# QuadroMIDI.net
KiCad netlist of a schematic drawn in EAGLE
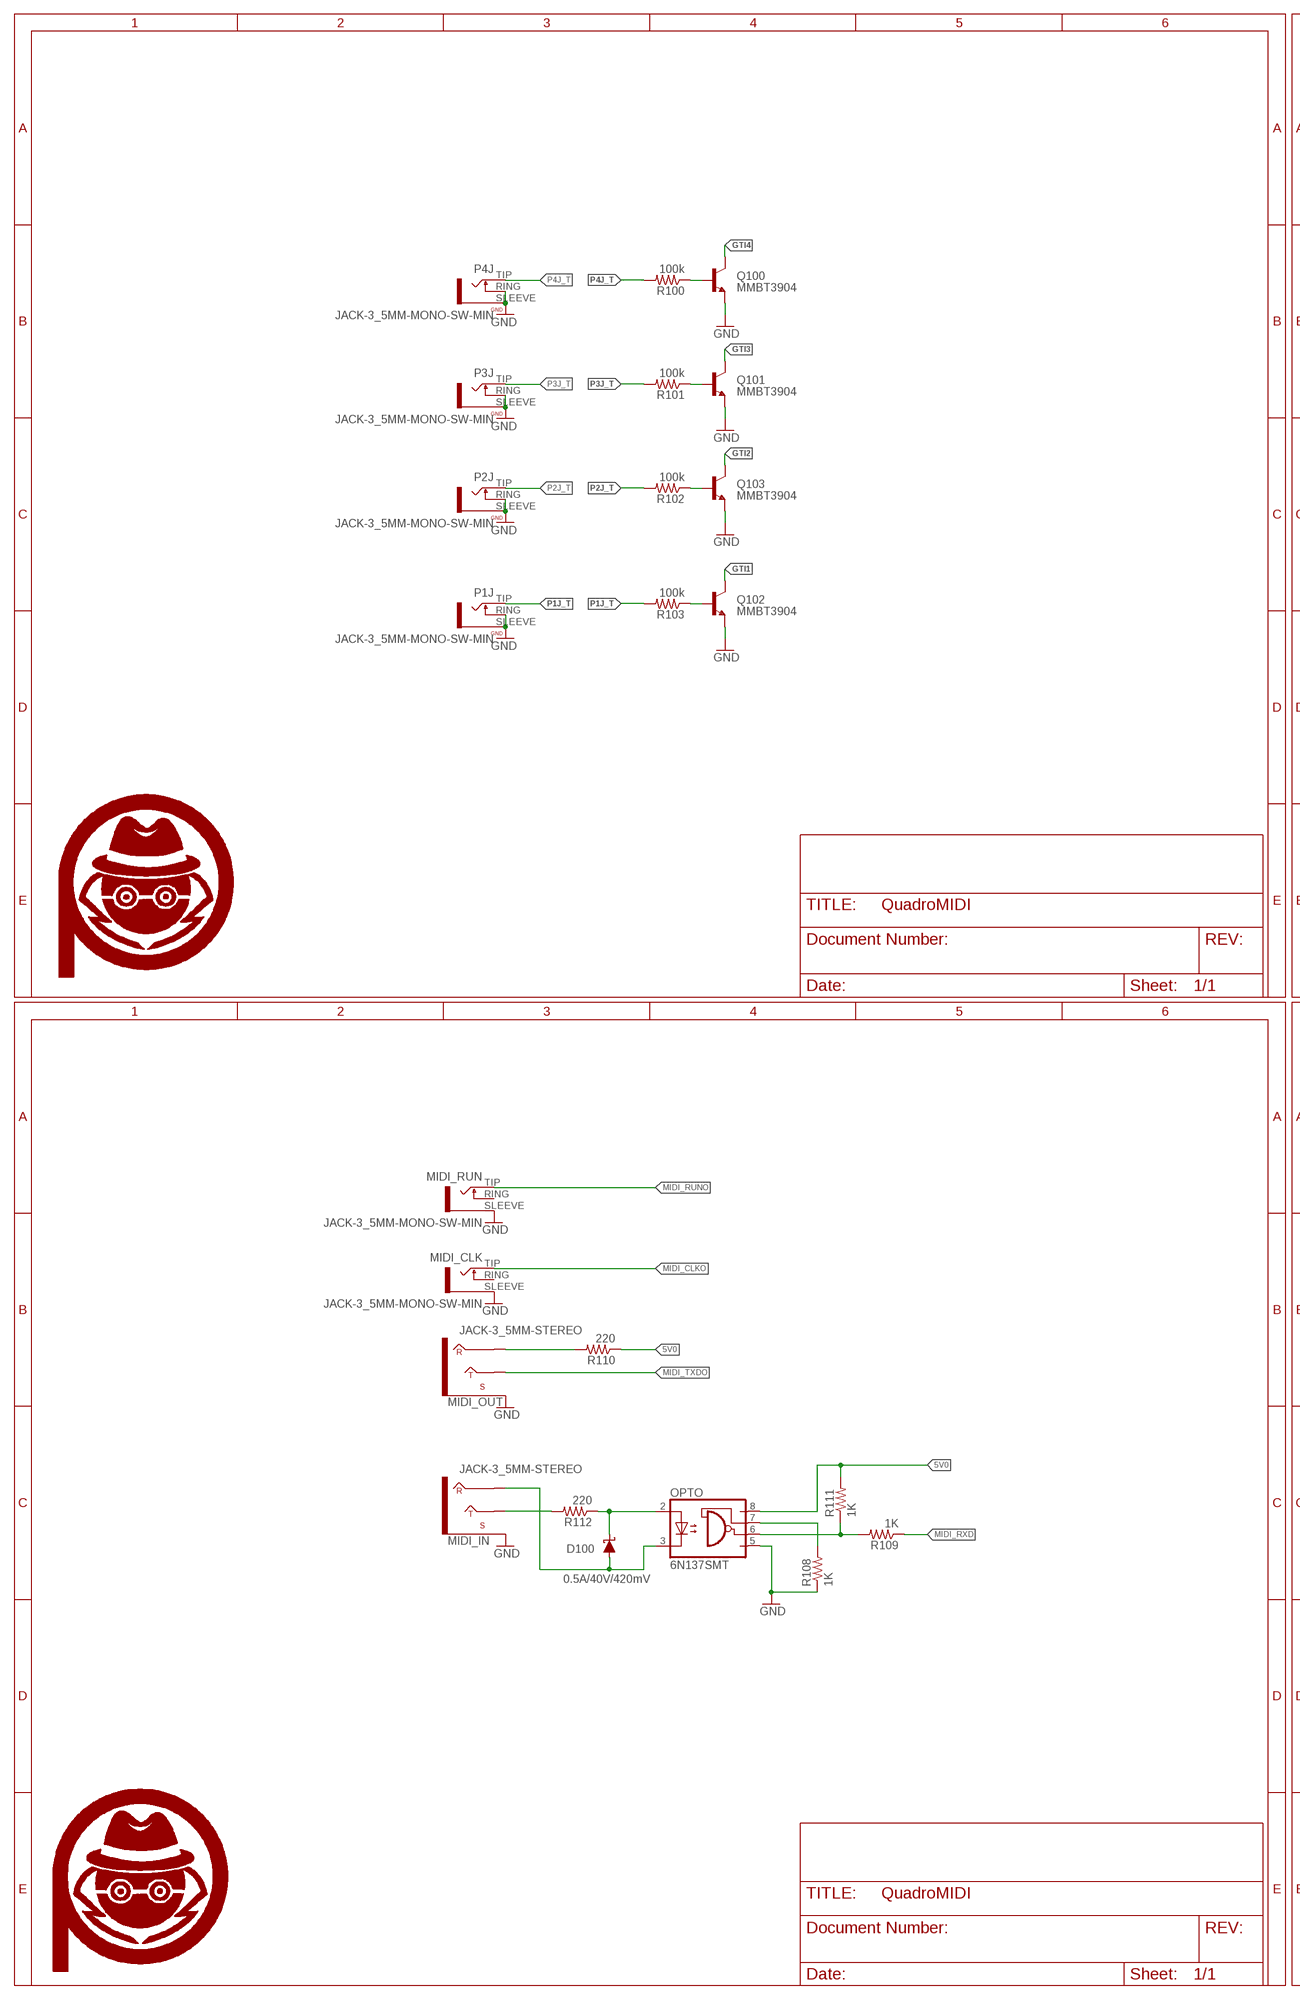
[diagram p0: schematic, sheet 1, part 1 of 2]
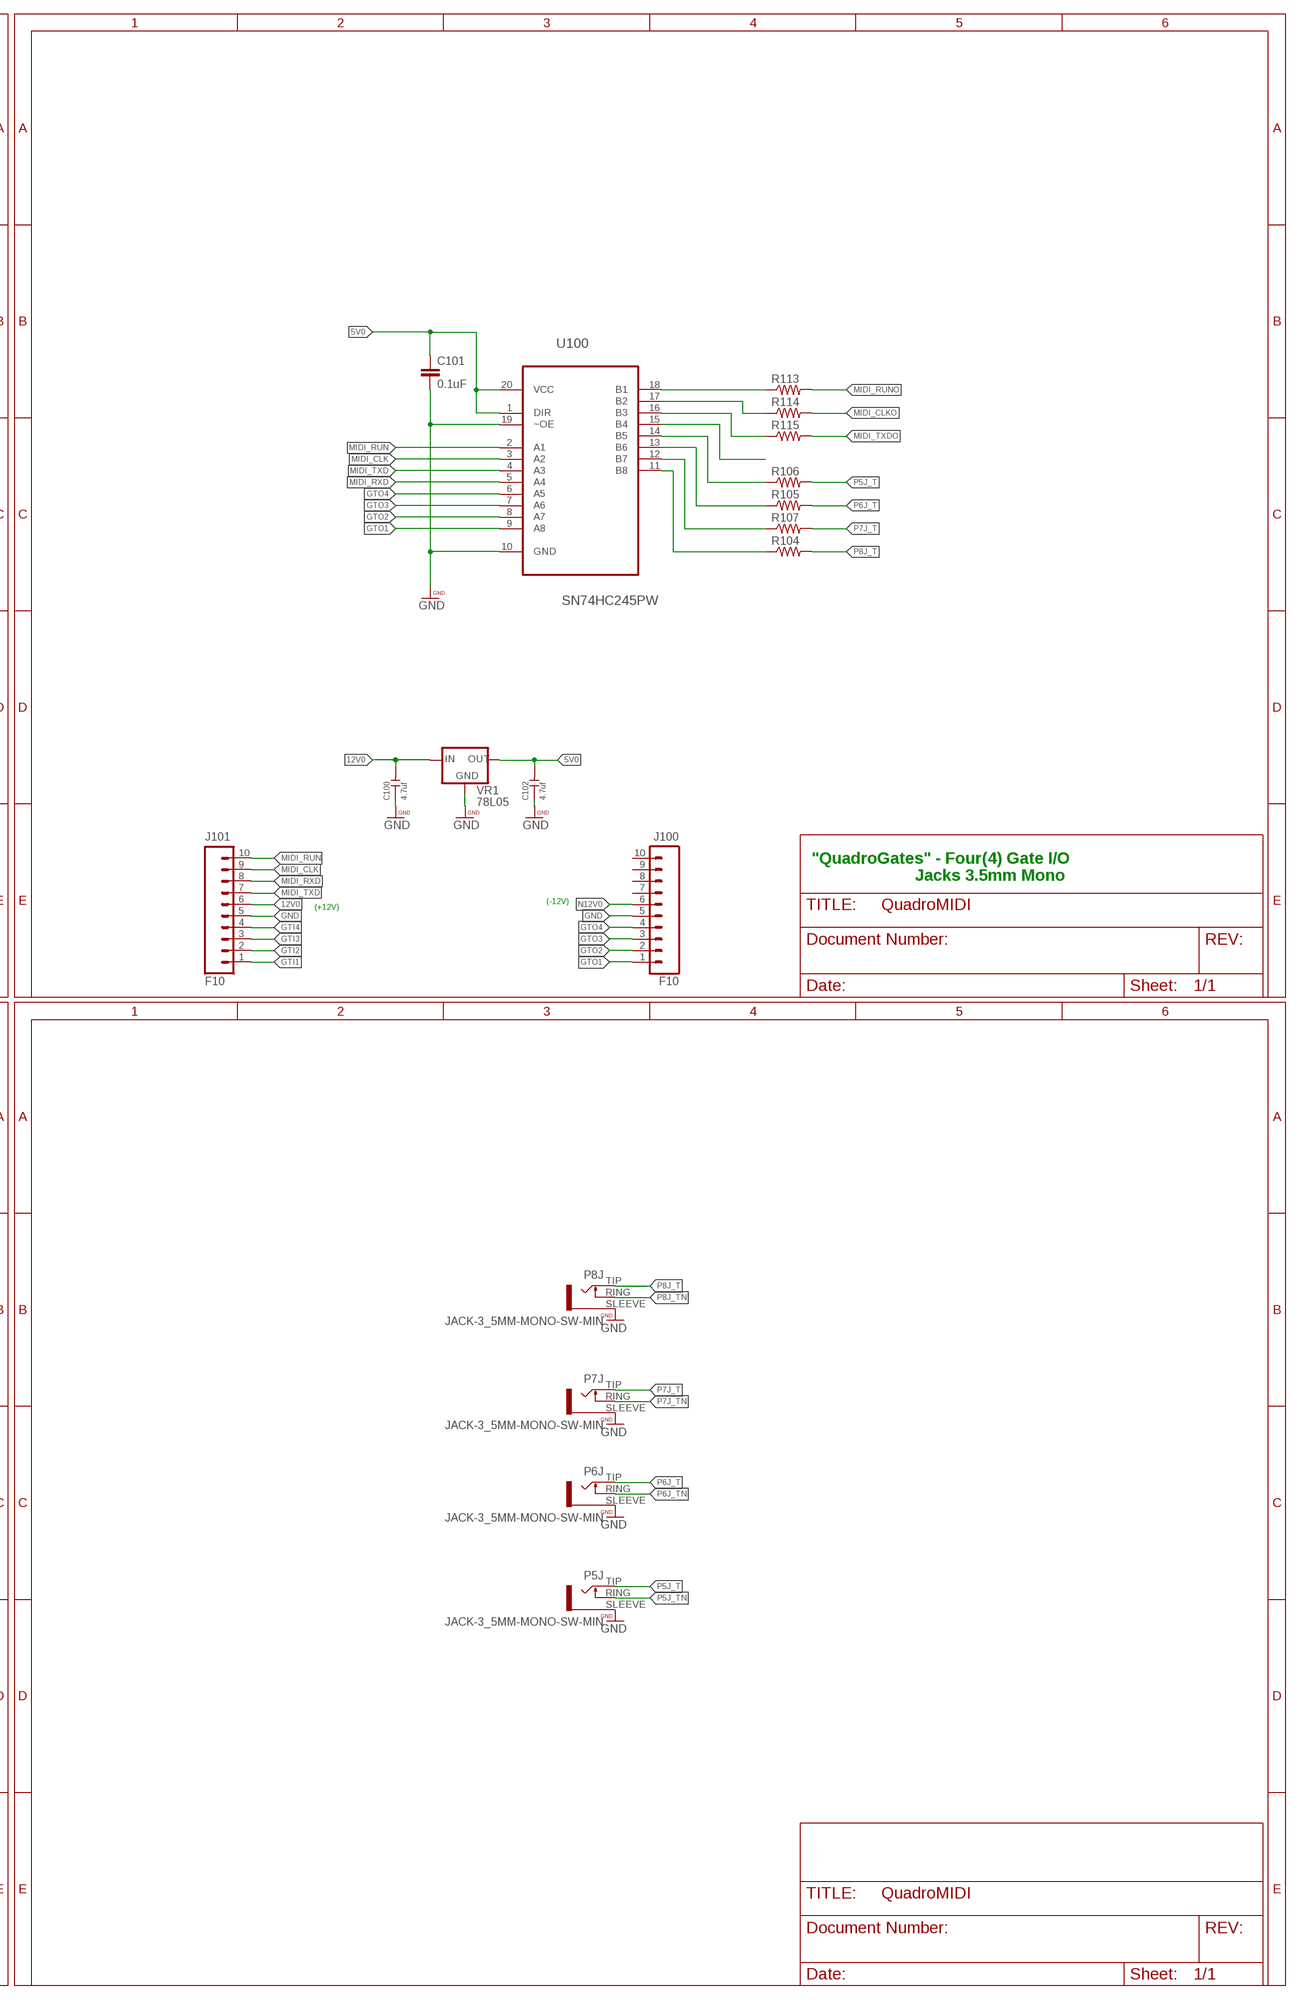
[diagram p1: schematic, sheet 1, part 2 of 2]

(export (version "E")
  (design (tool "Eeschema 10.0.6"))
  (components
    (comp (ref "$$U$1")
      (value "PA_LOGO_SYMLARGE")
      (footprint "eagle-import:PA_LOGO_AGENT_LRG_SYM")
      (libsource (lib "eagle-import") (part "PA_LOGO_SYMLARGE"))
    )
    (comp (ref "C100")
      (value "4.7uf")
      (footprint "eagle-import:C0805")
      (fields (field (name "MPN") "CC0805KKX5R8BB475"))
      (libsource (lib "eagle-import") (part "CERAMIC-4.7UF-25V-10%-X5R(0805)"))
    )
    (comp (ref "C101")
      (value "0.1uF")
      (footprint "eagle-import:0603-CAP")
      (libsource (lib "eagle-import") (part "CAP0603-CAP"))
    )
    (comp (ref "C102")
      (value "4.7uf")
      (footprint "eagle-import:C0805")
      (fields (field (name "MPN") "CC0805KKX5R8BB475"))
      (libsource (lib "eagle-import") (part "CERAMIC-4.7UF-25V-10%-X5R(0805)"))
    )
    (comp (ref "D100")
      (value "0.5A/40V/420mV")
      (footprint "eagle-import:SOD-323")
      (libsource (lib "eagle-import") (part "DIODE-SCHOTTKY-PMEG4005EJ"))
    )
    (comp (ref "J100")
      (value "F10")
      (footprint "eagle-import:1X10_OCTO")
      (libsource (lib "eagle-import") (part "M10SILK_FEMALE_PTH"))
    )
    (comp (ref "J101")
      (value "F10")
      (footprint "eagle-import:1X10_OCTO")
      (libsource (lib "eagle-import") (part "M10SILK_FEMALE_PTH"))
    )
    (comp (ref "MIDI_CLK")
      (value "JACK-3_5MM-MONO-SW-MIN")
      (footprint "eagle-import:WQP_PJ301M-MIN")
      (libsource (lib "eagle-import") (part "JACK-3_5MM-MONO-SW-MIN"))
    )
    (comp (ref "MIDI_IN")
      (value "JACK-3_5MM-STEREO")
      (footprint "eagle-import:WQP_PJ301M-MIN")
      (libsource (lib "eagle-import") (part "JACK-3_5MM-STEREO"))
    )
    (comp (ref "MIDI_OUT")
      (value "JACK-3_5MM-STEREO")
      (footprint "eagle-import:WQP_PJ301M-MIN")
      (libsource (lib "eagle-import") (part "JACK-3_5MM-STEREO"))
    )
    (comp (ref "MIDI_RUN")
      (value "JACK-3_5MM-MONO-SW-MIN")
      (footprint "eagle-import:WQP_PJ301M-MIN")
      (libsource (lib "eagle-import") (part "JACK-3_5MM-MONO-SW-MIN"))
    )
    (comp (ref "OPTO")
      (value "6N137SMT")
      (footprint "eagle-import:DIL8-SMD")
      (libsource (lib "eagle-import") (part "6N137SMT"))
    )
    (comp (ref "P1J")
      (value "JACK-3_5MM-MONO-SW-MIN")
      (footprint "eagle-import:WQP_PJ301M-MIN")
      (libsource (lib "eagle-import") (part "JACK-3_5MM-MONO-SW-MIN"))
    )
    (comp (ref "P2J")
      (value "JACK-3_5MM-MONO-SW-MIN")
      (footprint "eagle-import:WQP_PJ301M-MIN")
      (libsource (lib "eagle-import") (part "JACK-3_5MM-MONO-SW-MIN"))
    )
    (comp (ref "P3J")
      (value "JACK-3_5MM-MONO-SW-MIN")
      (footprint "eagle-import:WQP_PJ301M-MIN")
      (libsource (lib "eagle-import") (part "JACK-3_5MM-MONO-SW-MIN"))
    )
    (comp (ref "P4J")
      (value "JACK-3_5MM-MONO-SW-MIN")
      (footprint "eagle-import:WQP_PJ301M-MIN")
      (libsource (lib "eagle-import") (part "JACK-3_5MM-MONO-SW-MIN"))
    )
    (comp (ref "P5J")
      (value "JACK-3_5MM-MONO-SW-MIN")
      (footprint "eagle-import:WQP_PJ301M-MIN")
      (libsource (lib "eagle-import") (part "JACK-3_5MM-MONO-SW-MIN"))
    )
    (comp (ref "P6J")
      (value "JACK-3_5MM-MONO-SW-MIN")
      (footprint "eagle-import:WQP_PJ301M-MIN")
      (libsource (lib "eagle-import") (part "JACK-3_5MM-MONO-SW-MIN"))
    )
    (comp (ref "P7J")
      (value "JACK-3_5MM-MONO-SW-MIN")
      (footprint "eagle-import:WQP_PJ301M-MIN")
      (libsource (lib "eagle-import") (part "JACK-3_5MM-MONO-SW-MIN"))
    )
    (comp (ref "P8J")
      (value "JACK-3_5MM-MONO-SW-MIN")
      (footprint "eagle-import:WQP_PJ301M-MIN")
      (libsource (lib "eagle-import") (part "JACK-3_5MM-MONO-SW-MIN"))
    )
    (comp (ref "Q100")
      (value "MMBT3904")
      (footprint "eagle-import:SOT23-BEC")
      (libsource (lib "eagle-import") (part "-NPN-SOT23-BECMMBT3904LT1"))
    )
    (comp (ref "Q101")
      (value "MMBT3904")
      (footprint "eagle-import:SOT23-BEC")
      (libsource (lib "eagle-import") (part "-NPN-SOT23-BECMMBT3904LT1"))
    )
    (comp (ref "Q102")
      (value "MMBT3904")
      (footprint "eagle-import:SOT23-BEC")
      (libsource (lib "eagle-import") (part "-NPN-SOT23-BECMMBT3904LT1"))
    )
    (comp (ref "Q103")
      (value "MMBT3904")
      (footprint "eagle-import:SOT23-BEC")
      (libsource (lib "eagle-import") (part "-NPN-SOT23-BECMMBT3904LT1"))
    )
    (comp (ref "R100")
      (value "100k")
      (footprint "eagle-import:R0603")
      (libsource (lib "eagle-import") (part "R-US_R0603"))
    )
    (comp (ref "R101")
      (value "100k")
      (footprint "eagle-import:R0603")
      (libsource (lib "eagle-import") (part "R-US_R0603"))
    )
    (comp (ref "R102")
      (value "100k")
      (footprint "eagle-import:R0603")
      (libsource (lib "eagle-import") (part "R-US_R0603"))
    )
    (comp (ref "R103")
      (value "100k")
      (footprint "eagle-import:R0603")
      (libsource (lib "eagle-import") (part "R-US_R0603"))
    )
    (comp (ref "R104")
      (value "RESISTOR0603-RES")
      (footprint "eagle-import:0603-RES")
      (libsource (lib "eagle-import") (part "RESISTOR0603-RES"))
    )
    (comp (ref "R105")
      (value "RESISTOR0603-RES")
      (footprint "eagle-import:0603-RES")
      (libsource (lib "eagle-import") (part "RESISTOR0603-RES"))
    )
    (comp (ref "R106")
      (value "RESISTOR0603-RES")
      (footprint "eagle-import:0603-RES")
      (libsource (lib "eagle-import") (part "RESISTOR0603-RES"))
    )
    (comp (ref "R107")
      (value "RESISTOR0603-RES")
      (footprint "eagle-import:0603-RES")
      (libsource (lib "eagle-import") (part "RESISTOR0603-RES"))
    )
    (comp (ref "R108")
      (value "1K")
      (footprint "eagle-import:0603-RES")
      (libsource (lib "eagle-import") (part "RESISTOR0603"))
    )
    (comp (ref "R109")
      (value "1K")
      (footprint "eagle-import:0603-RES")
      (libsource (lib "eagle-import") (part "RESISTOR0603"))
    )
    (comp (ref "R110")
      (value "220")
      (footprint "eagle-import:0603-RES")
      (libsource (lib "eagle-import") (part "RESISTOR0603"))
    )
    (comp (ref "R111")
      (value "1K")
      (footprint "eagle-import:0603-RES")
      (libsource (lib "eagle-import") (part "RESISTOR0603"))
    )
    (comp (ref "R112")
      (value "220")
      (footprint "eagle-import:0603-RES")
      (libsource (lib "eagle-import") (part "RESISTOR0603"))
    )
    (comp (ref "R113")
      (value "RESISTOR0603-RES")
      (footprint "eagle-import:0603-RES")
      (libsource (lib "eagle-import") (part "RESISTOR0603-RES"))
    )
    (comp (ref "R114")
      (value "RESISTOR0603-RES")
      (footprint "eagle-import:0603-RES")
      (libsource (lib "eagle-import") (part "RESISTOR0603-RES"))
    )
    (comp (ref "R115")
      (value "RESISTOR0603-RES")
      (footprint "eagle-import:0603-RES")
      (libsource (lib "eagle-import") (part "RESISTOR0603-RES"))
    )
    (comp (ref "U$100")
      (value "PA_LOGO_SYMSMALL")
      (footprint "eagle-import:PA_LOGO_AGENT_SMALL_SYM")
      (libsource (lib "eagle-import") (part "PA_LOGO_SYMSMALL"))
    )
    (comp (ref "U100")
      (value "SN74HC245PW")
      (footprint "eagle-import:SOP65P640X120-20N")
      (libsource (lib "eagle-import") (part "SN74HC245PW"))
    )
    (comp (ref "VR1")
      (value "78L05")
      (footprint "eagle-import:SOT89")
      (libsource (lib "eagle-import") (part "78LXX-SOT89"))
    )
  )
  (nets
    (net (code "1") (name "5V0") (class "Default")
      (node (ref "C101") (pin "1") (pinfunction "1_1") (pintype "passive"))
      (node (ref "C102") (pin "2") (pinfunction "2_2") (pintype "passive"))
      (node (ref "OPTO") (pin "8") (pinfunction "VCC_8") (pintype "passive"))
      (node (ref "R110") (pin "1") (pinfunction "1_1") (pintype "passive"))
      (node (ref "R111") (pin "2") (pinfunction "2_2") (pintype "passive"))
      (node (ref "U100") (pin "1") (pinfunction "DIR_1") (pintype "input"))
      (node (ref "U100") (pin "20") (pinfunction "VCC_20") (pintype "power_in"))
      (node (ref "VR1") (pin "1") (pinfunction "OUT_1") (pintype "passive"))
    )
    (net (code "2") (name "12V0") (class "Default")
      (node (ref "C100") (pin "2") (pinfunction "2_2") (pintype "passive"))
      (node (ref "J101") (pin "6") (pinfunction "6_6") (pintype "passive"))
      (node (ref "VR1") (pin "3") (pinfunction "IN_3") (pintype "input"))
    )
    (net (code "3") (name "GND") (class "Default")
      (node (ref "C100") (pin "1") (pinfunction "1_1") (pintype "passive"))
      (node (ref "C101") (pin "2") (pinfunction "2_2") (pintype "passive"))
      (node (ref "C102") (pin "1") (pinfunction "1_1") (pintype "passive"))
      (node (ref "J100") (pin "5") (pinfunction "5_5") (pintype "passive"))
      (node (ref "J101") (pin "5") (pinfunction "5_5") (pintype "passive"))
      (node (ref "MIDI_CLK") (pin "SLEEVE") (pinfunction "SLEEVE_SLEEVE") (pintype "passive"))
      (node (ref "MIDI_IN") (pin "SLEEVE") (pinfunction "SLEEVE_SLEEVE") (pintype "bidirectional"))
      (node (ref "MIDI_OUT") (pin "SLEEVE") (pinfunction "SLEEVE_SLEEVE") (pintype "bidirectional"))
      (node (ref "MIDI_RUN") (pin "SLEEVE") (pinfunction "SLEEVE_SLEEVE") (pintype "passive"))
      (node (ref "OPTO") (pin "5") (pinfunction "GND_5") (pintype "passive"))
      (node (ref "P1J") (pin "RING") (pinfunction "TIP_SW_RING") (pintype "passive"))
      (node (ref "P1J") (pin "SLEEVE") (pinfunction "SLEEVE_SLEEVE") (pintype "passive"))
      (node (ref "P2J") (pin "RING") (pinfunction "TIP_SW_RING") (pintype "passive"))
      (node (ref "P2J") (pin "SLEEVE") (pinfunction "SLEEVE_SLEEVE") (pintype "passive"))
      (node (ref "P3J") (pin "RING") (pinfunction "TIP_SW_RING") (pintype "passive"))
      (node (ref "P3J") (pin "SLEEVE") (pinfunction "SLEEVE_SLEEVE") (pintype "passive"))
      (node (ref "P4J") (pin "RING") (pinfunction "TIP_SW_RING") (pintype "passive"))
      (node (ref "P4J") (pin "SLEEVE") (pinfunction "SLEEVE_SLEEVE") (pintype "passive"))
      (node (ref "P5J") (pin "SLEEVE") (pinfunction "SLEEVE_SLEEVE") (pintype "passive"))
      (node (ref "P6J") (pin "SLEEVE") (pinfunction "SLEEVE_SLEEVE") (pintype "passive"))
      (node (ref "P7J") (pin "SLEEVE") (pinfunction "SLEEVE_SLEEVE") (pintype "passive"))
      (node (ref "P8J") (pin "SLEEVE") (pinfunction "SLEEVE_SLEEVE") (pintype "passive"))
      (node (ref "Q100") (pin "E") (pinfunction "E_E") (pintype "passive"))
      (node (ref "Q101") (pin "E") (pinfunction "E_E") (pintype "passive"))
      (node (ref "Q102") (pin "E") (pinfunction "E_E") (pintype "passive"))
      (node (ref "Q103") (pin "E") (pinfunction "E_E") (pintype "passive"))
      (node (ref "R108") (pin "1") (pinfunction "1_1") (pintype "passive"))
      (node (ref "U100") (pin "10") (pinfunction "GND_10") (pintype "input"))
      (node (ref "U100") (pin "19") (pinfunction "~{OE}_19") (pintype "input"))
      (node (ref "VR1") (pin "2") (pinfunction "GND_2") (pintype "input"))
    )
    (net (code "4") (name "GTI1") (class "Default")
      (node (ref "J101") (pin "1") (pinfunction "1_1") (pintype "passive"))
      (node (ref "Q102") (pin "C") (pinfunction "C_C") (pintype "passive"))
    )
    (net (code "5") (name "GTI2") (class "Default")
      (node (ref "J101") (pin "2") (pinfunction "2_2") (pintype "passive"))
      (node (ref "Q103") (pin "C") (pinfunction "C_C") (pintype "passive"))
    )
    (net (code "6") (name "GTI3") (class "Default")
      (node (ref "J101") (pin "3") (pinfunction "3_3") (pintype "passive"))
      (node (ref "Q101") (pin "C") (pinfunction "C_C") (pintype "passive"))
    )
    (net (code "7") (name "GTI4") (class "Default")
      (node (ref "J101") (pin "4") (pinfunction "4_4") (pintype "passive"))
      (node (ref "Q100") (pin "C") (pinfunction "C_C") (pintype "passive"))
    )
    (net (code "8") (name "GTO1") (class "Default")
      (node (ref "J100") (pin "1") (pinfunction "1_1") (pintype "passive"))
      (node (ref "U100") (pin "9") (pinfunction "A8_9") (pintype "bidirectional"))
    )
    (net (code "9") (name "GTO2") (class "Default")
      (node (ref "J100") (pin "2") (pinfunction "2_2") (pintype "passive"))
      (node (ref "U100") (pin "8") (pinfunction "A7_8") (pintype "bidirectional"))
    )
    (net (code "10") (name "GTO3") (class "Default")
      (node (ref "J100") (pin "3") (pinfunction "3_3") (pintype "passive"))
      (node (ref "U100") (pin "7") (pinfunction "A6_7") (pintype "bidirectional"))
    )
    (net (code "11") (name "GTO4") (class "Default")
      (node (ref "J100") (pin "4") (pinfunction "4_4") (pintype "passive"))
      (node (ref "U100") (pin "6") (pinfunction "A5_6") (pintype "bidirectional"))
    )
    (net (code "12") (name "MIDI_CLK") (class "Default")
      (node (ref "J101") (pin "9") (pinfunction "9_9") (pintype "passive"))
      (node (ref "U100") (pin "3") (pinfunction "A2_3") (pintype "bidirectional"))
    )
    (net (code "13") (name "MIDI_CLKO") (class "Default")
      (node (ref "MIDI_CLK") (pin "TIP") (pinfunction "TIP_TIP") (pintype "passive"))
      (node (ref "R114") (pin "2") (pinfunction "2_2") (pintype "passive"))
    )
    (net (code "14") (name "MIDI_RUN") (class "Default")
      (node (ref "J101") (pin "10") (pinfunction "10_10") (pintype "passive"))
      (node (ref "U100") (pin "2") (pinfunction "A1_2") (pintype "bidirectional"))
    )
    (net (code "15") (name "MIDI_RUNO") (class "Default")
      (node (ref "MIDI_RUN") (pin "TIP") (pinfunction "TIP_TIP") (pintype "passive"))
      (node (ref "R113") (pin "2") (pinfunction "2_2") (pintype "passive"))
    )
    (net (code "16") (name "MIDI_RXD") (class "Default")
      (node (ref "J101") (pin "8") (pinfunction "8_8") (pintype "passive"))
      (node (ref "R109") (pin "1") (pinfunction "1_1") (pintype "passive"))
      (node (ref "U100") (pin "5") (pinfunction "A4_5") (pintype "bidirectional"))
    )
    (net (code "17") (name "MIDI_TXD") (class "Default")
      (node (ref "J101") (pin "7") (pinfunction "7_7") (pintype "passive"))
      (node (ref "U100") (pin "4") (pinfunction "A3_4") (pintype "bidirectional"))
    )
    (net (code "18") (name "MIDI_TXDO") (class "Default")
      (node (ref "MIDI_OUT") (pin "TIP") (pinfunction "TIP_TIP") (pintype "bidirectional"))
      (node (ref "R115") (pin "2") (pinfunction "2_2") (pintype "passive"))
    )
    (net (code "19") (name "N12V0") (class "Default")
      (node (ref "J100") (pin "6") (pinfunction "6_6") (pintype "passive"))
    )
    (net (code "20") (name "Net-(MIDI_IN-PadTIP)") (class "Default")
      (node (ref "MIDI_IN") (pin "TIP") (pinfunction "TIP_TIP") (pintype "bidirectional"))
      (node (ref "R112") (pin "2") (pinfunction "2_2") (pintype "passive"))
    )
    (net (code "21") (name "Net-(MIDI_OUT-PadRING)") (class "Default")
      (node (ref "MIDI_OUT") (pin "RING") (pinfunction "RING_RING") (pintype "bidirectional"))
      (node (ref "R110") (pin "2") (pinfunction "2_2") (pintype "passive"))
    )
    (net (code "22") (name "Net-(OPTO-A)") (class "Default")
      (node (ref "D100") (pin "C") (pinfunction "C_C") (pintype "passive"))
      (node (ref "OPTO") (pin "2") (pinfunction "A_2") (pintype "passive"))
      (node (ref "R112") (pin "1") (pinfunction "1_1") (pintype "passive"))
    )
    (net (code "23") (name "Net-(OPTO-C)") (class "Default")
      (node (ref "D100") (pin "A") (pinfunction "A_A") (pintype "passive"))
      (node (ref "MIDI_IN") (pin "RING") (pinfunction "RING_RING") (pintype "bidirectional"))
      (node (ref "OPTO") (pin "3") (pinfunction "C_3") (pintype "passive"))
    )
    (net (code "24") (name "Net-(OPTO-VE)") (class "Default")
      (node (ref "OPTO") (pin "7") (pinfunction "VE_7") (pintype "passive"))
      (node (ref "R108") (pin "2") (pinfunction "2_2") (pintype "passive"))
    )
    (net (code "25") (name "Net-(OPTO-VO)") (class "Default")
      (node (ref "OPTO") (pin "6") (pinfunction "VO_6") (pintype "passive"))
      (node (ref "R109") (pin "2") (pinfunction "2_2") (pintype "passive"))
      (node (ref "R111") (pin "1") (pinfunction "1_1") (pintype "passive"))
    )
    (net (code "26") (name "Net-(Q100-PadB)") (class "Default")
      (node (ref "Q100") (pin "B") (pinfunction "B_B") (pintype "passive"))
      (node (ref "R100") (pin "1") (pinfunction "1_1") (pintype "passive"))
    )
    (net (code "27") (name "Net-(Q101-PadB)") (class "Default")
      (node (ref "Q101") (pin "B") (pinfunction "B_B") (pintype "passive"))
      (node (ref "R101") (pin "1") (pinfunction "1_1") (pintype "passive"))
    )
    (net (code "28") (name "Net-(Q102-PadB)") (class "Default")
      (node (ref "Q102") (pin "B") (pinfunction "B_B") (pintype "passive"))
      (node (ref "R103") (pin "1") (pinfunction "1_1") (pintype "passive"))
    )
    (net (code "29") (name "Net-(Q103-PadB)") (class "Default")
      (node (ref "Q103") (pin "B") (pinfunction "B_B") (pintype "passive"))
      (node (ref "R102") (pin "1") (pinfunction "1_1") (pintype "passive"))
    )
    (net (code "30") (name "Net-(U100-B1)") (class "Default")
      (node (ref "R113") (pin "1") (pinfunction "1_1") (pintype "passive"))
      (node (ref "U100") (pin "18") (pinfunction "B1_18") (pintype "bidirectional"))
    )
    (net (code "31") (name "Net-(U100-B2)") (class "Default")
      (node (ref "R114") (pin "1") (pinfunction "1_1") (pintype "passive"))
      (node (ref "U100") (pin "17") (pinfunction "B2_17") (pintype "bidirectional"))
    )
    (net (code "32") (name "Net-(U100-B3)") (class "Default")
      (node (ref "R115") (pin "1") (pinfunction "1_1") (pintype "passive"))
      (node (ref "U100") (pin "16") (pinfunction "B3_16") (pintype "bidirectional"))
    )
    (net (code "33") (name "Net-(U100-B5)") (class "Default")
      (node (ref "R106") (pin "1") (pinfunction "1_1") (pintype "passive"))
      (node (ref "U100") (pin "14") (pinfunction "B5_14") (pintype "bidirectional"))
    )
    (net (code "34") (name "Net-(U100-B6)") (class "Default")
      (node (ref "R105") (pin "1") (pinfunction "1_1") (pintype "passive"))
      (node (ref "U100") (pin "13") (pinfunction "B6_13") (pintype "bidirectional"))
    )
    (net (code "35") (name "Net-(U100-B7)") (class "Default")
      (node (ref "R107") (pin "1") (pinfunction "1_1") (pintype "passive"))
      (node (ref "U100") (pin "12") (pinfunction "B7_12") (pintype "bidirectional"))
    )
    (net (code "36") (name "Net-(U100-B8)") (class "Default")
      (node (ref "R104") (pin "1") (pinfunction "1_1") (pintype "passive"))
      (node (ref "U100") (pin "11") (pinfunction "B8_11") (pintype "bidirectional"))
    )
    (net (code "37") (name "P1J_T") (class "Default")
      (node (ref "P1J") (pin "TIP") (pinfunction "TIP_TIP") (pintype "passive"))
      (node (ref "R103") (pin "2") (pinfunction "2_2") (pintype "passive"))
    )
    (net (code "38") (name "P2J_T") (class "Default")
      (node (ref "P2J") (pin "TIP") (pinfunction "TIP_TIP") (pintype "passive"))
      (node (ref "R102") (pin "2") (pinfunction "2_2") (pintype "passive"))
    )
    (net (code "39") (name "P3J_T") (class "Default")
      (node (ref "P3J") (pin "TIP") (pinfunction "TIP_TIP") (pintype "passive"))
      (node (ref "R101") (pin "2") (pinfunction "2_2") (pintype "passive"))
    )
    (net (code "40") (name "P4J_T") (class "Default")
      (node (ref "P4J") (pin "TIP") (pinfunction "TIP_TIP") (pintype "passive"))
      (node (ref "R100") (pin "2") (pinfunction "2_2") (pintype "passive"))
    )
    (net (code "41") (name "P5J_T") (class "Default")
      (node (ref "P5J") (pin "TIP") (pinfunction "TIP_TIP") (pintype "passive"))
      (node (ref "R106") (pin "2") (pinfunction "2_2") (pintype "passive"))
    )
    (net (code "42") (name "P5J_TN") (class "Default")
      (node (ref "P5J") (pin "RING") (pinfunction "TIP_SW_RING") (pintype "passive"))
    )
    (net (code "43") (name "P6J_T") (class "Default")
      (node (ref "P6J") (pin "TIP") (pinfunction "TIP_TIP") (pintype "passive"))
      (node (ref "R105") (pin "2") (pinfunction "2_2") (pintype "passive"))
    )
    (net (code "44") (name "P6J_TN") (class "Default")
      (node (ref "P6J") (pin "RING") (pinfunction "TIP_SW_RING") (pintype "passive"))
    )
    (net (code "45") (name "P7J_T") (class "Default")
      (node (ref "P7J") (pin "TIP") (pinfunction "TIP_TIP") (pintype "passive"))
      (node (ref "R107") (pin "2") (pinfunction "2_2") (pintype "passive"))
    )
    (net (code "46") (name "P7J_TN") (class "Default")
      (node (ref "P7J") (pin "RING") (pinfunction "TIP_SW_RING") (pintype "passive"))
    )
    (net (code "47") (name "P8J_T") (class "Default")
      (node (ref "P8J") (pin "TIP") (pinfunction "TIP_TIP") (pintype "passive"))
      (node (ref "R104") (pin "2") (pinfunction "2_2") (pintype "passive"))
    )
    (net (code "48") (name "P8J_TN") (class "Default")
      (node (ref "P8J") (pin "RING") (pinfunction "TIP_SW_RING") (pintype "passive"))
    )
    (net (code "49") (name "unconnected-(J100-Pad7)") (class "Default")
      (node (ref "J100") (pin "7") (pinfunction "7_7") (pintype "passive"))
    )
    (net (code "50") (name "unconnected-(J100-Pad8)") (class "Default")
      (node (ref "J100") (pin "8") (pinfunction "8_8") (pintype "passive"))
    )
    (net (code "51") (name "unconnected-(J100-Pad9)") (class "Default")
      (node (ref "J100") (pin "9") (pinfunction "9_9") (pintype "passive"))
    )
    (net (code "52") (name "unconnected-(J100-Pad10)") (class "Default")
      (node (ref "J100") (pin "10") (pinfunction "10_10") (pintype "passive"))
    )
    (net (code "53") (name "unconnected-(MIDI_CLK-TIP_SW-PadRING)") (class "Default")
      (node (ref "MIDI_CLK") (pin "RING") (pinfunction "TIP_SW_RING") (pintype "passive"))
    )
    (net (code "54") (name "unconnected-(MIDI_RUN-TIP_SW-PadRING)") (class "Default")
      (node (ref "MIDI_RUN") (pin "RING") (pinfunction "TIP_SW_RING") (pintype "passive"))
    )
    (net (code "55") (name "unconnected-(U100-B4-Pad15)") (class "Default")
      (node (ref "U100") (pin "15") (pinfunction "B4_15") (pintype "bidirectional"))
    )
  )
)
